# USB_Isolator.net
KiCad netlist of a schematic drawn in Altium Designer
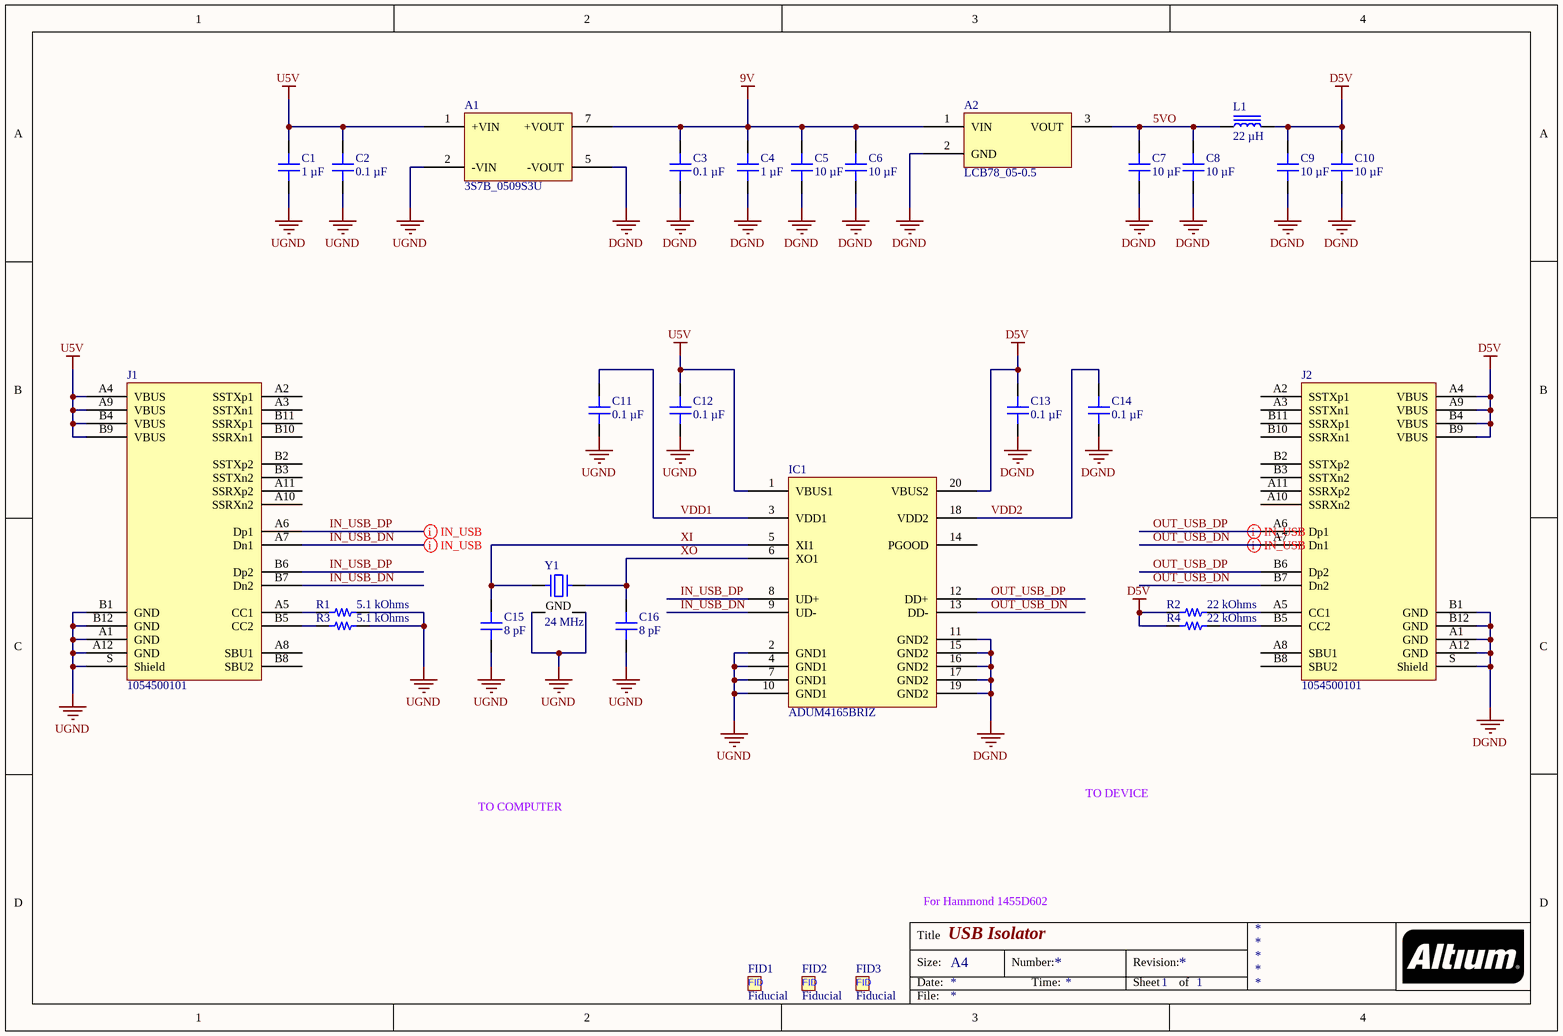
[diagram p0: USB Isolator.SchDoc]

(export (version "E")
  (design (tool "Eeschema 10.0.6"))
  (components
    (comp (ref "A1")
      (value "3S7B_0509S3U")
      (footprint "GAPTEC 3S7B_3U SINGLE")
      (description "DC-DC")
      (fields (field (name "MANUFACTURER") "GAPTEC Electronic"))
      (libsource (lib "altiumlibrary.com") (part "GAPTEC 3S7B_3U SINGLE"))
    )
    (comp (ref "A2")
      (value "LCB78_05-0.5")
      (footprint "GAPTEC LCB78_0.5")
      (description "DC-DC POL")
      (fields (field (name "MANUFACTURER") "GAPTEC Electronic"))
      (libsource (lib "altiumlibrary.com") (part "GAPTEC LCB78"))
    )
    (comp (ref "C1")
      (value "1 µF")
      (footprint "CAP 0603_1608")
      (description "CAP CER 1UF 25V X7R 0603")
      (fields
        (field (name "PART NUMBER") "GCM188R71E105KA64D")
        (field (name "MANUFACTURER") "Murata Electronics")
      )
      (libsource (lib "altiumlibrary.com") (part "Capacitor"))
    )
    (comp (ref "C2")
      (value "0.1 µF")
      (footprint "CAP 0603_1608")
      (description "CAP CER 0.1UF 50V X7R 0603")
      (fields
        (field (name "PART NUMBER") "CL10B104KB8NNNC")
        (field (name "MANUFACTURER") "Samsung Electro-Mechanics")
      )
      (libsource (lib "altiumlibrary.com") (part "Capacitor"))
    )
    (comp (ref "C3")
      (value "0.1 µF")
      (footprint "CAP 0603_1608")
      (description "CAP CER 0.1UF 50V X7R 0603")
      (fields
        (field (name "PART NUMBER") "CL10B104KB8NNNC")
        (field (name "MANUFACTURER") "Samsung Electro-Mechanics")
      )
      (libsource (lib "altiumlibrary.com") (part "Capacitor"))
    )
    (comp (ref "C4")
      (value "1 µF")
      (footprint "CAP 0603_1608")
      (description "CAP CER 1UF 25V X7R 0603")
      (fields
        (field (name "PART NUMBER") "GCM188R71E105KA64D")
        (field (name "MANUFACTURER") "Murata Electronics")
      )
      (libsource (lib "altiumlibrary.com") (part "Capacitor"))
    )
    (comp (ref "C5")
      (value "10 µF")
      (footprint "CAP 1206_3216 - 0.8MM")
      (description "CAP CER 10UF 25V X7R 1206")
      (fields
        (field (name "PART NUMBER") "CL31B106KAHNNNE")
        (field (name "MANUFACTURER") "Samsung Electro-Mechanics")
      )
      (libsource (lib "altiumlibrary.com") (part "Capacitor"))
    )
    (comp (ref "C6")
      (value "10 µF")
      (footprint "CAP 1206_3216 - 0.8MM")
      (description "CAP CER 10UF 25V X7R 1206")
      (fields
        (field (name "PART NUMBER") "CL31B106KAHNNNE")
        (field (name "MANUFACTURER") "Samsung Electro-Mechanics")
      )
      (libsource (lib "altiumlibrary.com") (part "Capacitor"))
    )
    (comp (ref "C7")
      (value "10 µF")
      (footprint "CAP 1206_3216 - 0.8MM")
      (description "CAP CER 10UF 25V X7R 1206")
      (fields
        (field (name "PART NUMBER") "CL31B106KAHNNNE")
        (field (name "MANUFACTURER") "Samsung Electro-Mechanics")
      )
      (libsource (lib "altiumlibrary.com") (part "Capacitor"))
    )
    (comp (ref "C8")
      (value "10 µF")
      (footprint "CAP 1206_3216 - 0.8MM")
      (description "CAP CER 10UF 25V X7R 1206")
      (fields
        (field (name "PART NUMBER") "CL31B106KAHNNNE")
        (field (name "MANUFACTURER") "Samsung Electro-Mechanics")
      )
      (libsource (lib "altiumlibrary.com") (part "Capacitor"))
    )
    (comp (ref "C9")
      (value "10 µF")
      (footprint "CAP 1206_3216 - 0.8MM")
      (description "CAP CER 10UF 25V X7R 1206")
      (fields
        (field (name "PART NUMBER") "CL31B106KAHNNNE")
        (field (name "MANUFACTURER") "Samsung Electro-Mechanics")
      )
      (libsource (lib "altiumlibrary.com") (part "Capacitor"))
    )
    (comp (ref "C10")
      (value "10 µF")
      (footprint "CAP 1206_3216 - 0.8MM")
      (description "CAP CER 10UF 25V X7R 1206")
      (fields
        (field (name "PART NUMBER") "CL31B106KAHNNNE")
        (field (name "MANUFACTURER") "Samsung Electro-Mechanics")
      )
      (libsource (lib "altiumlibrary.com") (part "Capacitor"))
    )
    (comp (ref "C11")
      (value "0.1 µF")
      (footprint "CAP 0603_1608")
      (description "CAP CER 0.1UF 50V X7R 0603")
      (fields
        (field (name "PART NUMBER") "CL10B104KB8NNNC")
        (field (name "MANUFACTURER") "Samsung Electro-Mechanics")
      )
      (libsource (lib "altiumlibrary.com") (part "Capacitor"))
    )
    (comp (ref "C12")
      (value "0.1 µF")
      (footprint "CAP 0603_1608")
      (description "CAP CER 0.1UF 50V X7R 0603")
      (fields
        (field (name "PART NUMBER") "CL10B104KB8NNNC")
        (field (name "MANUFACTURER") "Samsung Electro-Mechanics")
      )
      (libsource (lib "altiumlibrary.com") (part "Capacitor"))
    )
    (comp (ref "C13")
      (value "0.1 µF")
      (footprint "CAP 0603_1608")
      (description "CAP CER 0.1UF 50V X7R 0603")
      (fields
        (field (name "PART NUMBER") "CL10B104KB8NNNC")
        (field (name "MANUFACTURER") "Samsung Electro-Mechanics")
      )
      (libsource (lib "altiumlibrary.com") (part "Capacitor"))
    )
    (comp (ref "C14")
      (value "0.1 µF")
      (footprint "CAP 0603_1608")
      (description "CAP CER 0.1UF 50V X7R 0603")
      (fields
        (field (name "PART NUMBER") "CL10B104KB8NNNC")
        (field (name "MANUFACTURER") "Samsung Electro-Mechanics")
      )
      (libsource (lib "altiumlibrary.com") (part "Capacitor"))
    )
    (comp (ref "C15")
      (value "8 pF")
      (footprint "CAP 0603_1608")
      (description "CAP CER 8PF 50V C0G 0603")
      (fields
        (field (name "PART NUMBER") "CGA3E2C0G1H080D080AA")
        (field (name "MANUFACTURER") "TDK Corporation")
      )
      (libsource (lib "altiumlibrary.com") (part "Capacitor"))
    )
    (comp (ref "C16")
      (value "8 pF")
      (footprint "CAP 0603_1608")
      (description "CAP CER 8PF 50V C0G 0603")
      (fields
        (field (name "PART NUMBER") "CGA3E2C0G1H080D080AA")
        (field (name "MANUFACTURER") "TDK Corporation")
      )
      (libsource (lib "altiumlibrary.com") (part "Capacitor"))
    )
    (comp (ref "FID1")
      (value "Fiducial")
      (footprint "Fiducial-1mm")
      (libsource (lib "CelestialUseful") (part "Fiducial"))
    )
    (comp (ref "FID2")
      (value "Fiducial")
      (footprint "Fiducial-1mm")
      (libsource (lib "CelestialUseful") (part "Fiducial"))
    )
    (comp (ref "FID3")
      (value "Fiducial")
      (footprint "Fiducial-1mm")
      (libsource (lib "CelestialUseful") (part "Fiducial"))
    )
    (comp (ref "IC1")
      (value "ADUM4165BRIZ")
      (footprint "ANALOG SOIC-20 RI-20-1")
      (description "5KV 480MBPS USB DIG ISOLATOR HOS")
      (fields (field (name "MANUFACTURER") "Analog Devices Inc."))
      (libsource (lib "altiumlibrary.com") (part "ANALOG DEVICES ADUM4165"))
    )
    (comp (ref "J1")
      (value "1054500101")
      (footprint "Molex 1054500101")
      (description "CONN RCP USB3.1 TYPEC 24P SMD RA")
      (fields (field (name "MANUFACTURER") "Molex"))
      (libsource (lib "") (part "USB 3.0 Type C_1"))
    )
    (comp (ref "J2")
      (value "1054500101")
      (footprint "Molex 1054500101")
      (description "CONN RCP USB3.1 TYPEC 24P SMD RA")
      (fields (field (name "MANUFACTURER") "Molex"))
      (libsource (lib "altiumlibrary.com") (part "USB 3.0 Type C"))
    )
    (comp (ref "L1")
      (value "22 µH")
      (footprint "TDK VLCF4028-2")
      (description "FIXED IND 22UH 710MA 140MOHM SMD")
      (fields
        (field (name "PART NUMBER") "VLCF5028T-220MR71-2")
        (field (name "MANUFACTURER") "TDK Corporation")
      )
      (libsource (lib "altiumlibrary.com") (part "Inductor"))
    )
    (comp (ref "R1")
      (value "5.1 kOhms")
      (footprint "RES 0603_1608")
      (description "RES 5.1K OHM 1% 1/10W 0603")
      (fields
        (field (name "PART NUMBER") "RK73H1JTTD5101F")
        (field (name "MANUFACTURER") "KOA Speer Electronics, Inc.")
      )
      (libsource (lib "altiumlibrary.com") (part "Resistor"))
    )
    (comp (ref "R2")
      (value "22 kOhms")
      (footprint "RES 0603_1608")
      (description "RES 22K OHM 1% 1/10W 0603")
      (fields (field (name "PART NUMBER") "RC0603FR-1322KL") (field (name "MANUFACTURER") "Yageo"))
      (libsource (lib "altiumlibrary.com") (part "Resistor"))
    )
    (comp (ref "R3")
      (value "5.1 kOhms")
      (footprint "RES 0603_1608")
      (description "RES 5.1K OHM 1% 1/10W 0603")
      (fields
        (field (name "PART NUMBER") "RK73H1JTTD5101F")
        (field (name "MANUFACTURER") "KOA Speer Electronics, Inc.")
      )
      (libsource (lib "altiumlibrary.com") (part "Resistor"))
    )
    (comp (ref "R4")
      (value "22 kOhms")
      (footprint "RES 0603_1608")
      (description "RES 22K OHM 1% 1/10W 0603")
      (fields (field (name "PART NUMBER") "RC0603FR-1322KL") (field (name "MANUFACTURER") "Yageo"))
      (libsource (lib "altiumlibrary.com") (part "Resistor"))
    )
    (comp (ref "Y1")
      (value "24 MHz")
      (footprint "NDK NX2520SA")
      (description "CRYSTAL 24.0000MHZ 8PF SMD")
      (fields
        (field (name "PART NUMBER") "NX2520SA-24MHZ-EXS00A-CS11339")
        (field (name "MANUFACTURER") "NDK America, Inc.")
      )
      (libsource (lib "altiumlibrary.com") (part "NDK Crystal NX2520SA"))
    )
  )
  (nets
    (net (code "1") (name "/5VO") (class "Default")
      (node (ref "A2") (pin "3") (pinfunction "VOUT_3") (pintype "passive"))
      (node (ref "C7") (pin "2") (pinfunction "2_2") (pintype "passive"))
      (node (ref "C8") (pin "2") (pinfunction "2_2") (pintype "passive"))
      (node (ref "L1") (pin "1") (pinfunction "1_1") (pintype "passive"))
    )
    (net (code "2") (name "/IN_USB_DN") (class "Default")
      (node (ref "IC1") (pin "9") (pinfunction "UD-_9") (pintype "passive"))
      (node (ref "J1") (pin "A7") (pinfunction "Dn1_A7") (pintype "passive"))
      (node (ref "J1") (pin "B7") (pinfunction "Dn2_B7") (pintype "passive"))
    )
    (net (code "3") (name "/IN_USB_DP") (class "Default")
      (node (ref "IC1") (pin "8") (pinfunction "UD+_8") (pintype "passive"))
      (node (ref "J1") (pin "A6") (pinfunction "Dp1_A6") (pintype "passive"))
      (node (ref "J1") (pin "B6") (pinfunction "Dp2_B6") (pintype "passive"))
    )
    (net (code "4") (name "/OUT_USB_DN") (class "Default")
      (node (ref "IC1") (pin "13") (pinfunction "DD-_13") (pintype "passive"))
      (node (ref "J2") (pin "A7") (pinfunction "Dn1_A7") (pintype "passive"))
      (node (ref "J2") (pin "B7") (pinfunction "Dn2_B7") (pintype "passive"))
    )
    (net (code "5") (name "/OUT_USB_DP") (class "Default")
      (node (ref "IC1") (pin "12") (pinfunction "DD+_12") (pintype "passive"))
      (node (ref "J2") (pin "A6") (pinfunction "Dp1_A6") (pintype "passive"))
      (node (ref "J2") (pin "B6") (pinfunction "Dp2_B6") (pintype "passive"))
    )
    (net (code "6") (name "/VDD1") (class "Default")
      (node (ref "C11") (pin "2") (pinfunction "2_2") (pintype "passive"))
      (node (ref "IC1") (pin "3") (pinfunction "VDD1_3") (pintype "passive"))
    )
    (net (code "7") (name "/VDD2") (class "Default")
      (node (ref "C14") (pin "2") (pinfunction "2_2") (pintype "passive"))
      (node (ref "IC1") (pin "18") (pinfunction "VDD2_18") (pintype "passive"))
    )
    (net (code "8") (name "/XI") (class "Default")
      (node (ref "C15") (pin "2") (pinfunction "2_2") (pintype "passive"))
      (node (ref "IC1") (pin "5") (pinfunction "XI1_5") (pintype "passive"))
      (node (ref "Y1") (pin "1") (pinfunction "1_1") (pintype "passive"))
    )
    (net (code "9") (name "/XO") (class "Default")
      (node (ref "C16") (pin "2") (pinfunction "2_2") (pintype "passive"))
      (node (ref "IC1") (pin "6") (pinfunction "XO1_6") (pintype "passive"))
      (node (ref "Y1") (pin "3") (pinfunction "3_3") (pintype "passive"))
    )
    (net (code "10") (name "9V") (class "Default")
      (node (ref "A1") (pin "7") (pinfunction "+VOUT_7") (pintype "passive"))
      (node (ref "A2") (pin "1") (pinfunction "VIN_1") (pintype "passive"))
      (node (ref "C3") (pin "2") (pinfunction "2_2") (pintype "passive"))
      (node (ref "C4") (pin "2") (pinfunction "2_2") (pintype "passive"))
      (node (ref "C5") (pin "2") (pinfunction "2_2") (pintype "passive"))
      (node (ref "C6") (pin "2") (pinfunction "2_2") (pintype "passive"))
    )
    (net (code "11") (name "D5V") (class "Default")
      (node (ref "C10") (pin "2") (pinfunction "2_2") (pintype "passive"))
      (node (ref "C13") (pin "2") (pinfunction "2_2") (pintype "passive"))
      (node (ref "C9") (pin "2") (pinfunction "2_2") (pintype "passive"))
      (node (ref "IC1") (pin "20") (pinfunction "VBUS2_20") (pintype "passive"))
      (node (ref "J2") (pin "A4") (pinfunction "VBUS_A4") (pintype "passive"))
      (node (ref "J2") (pin "A9") (pinfunction "VBUS_A9") (pintype "passive"))
      (node (ref "J2") (pin "B4") (pinfunction "VBUS_B4") (pintype "passive"))
      (node (ref "J2") (pin "B9") (pinfunction "VBUS_B9") (pintype "passive"))
      (node (ref "L1") (pin "2") (pinfunction "2_2") (pintype "passive"))
      (node (ref "R2") (pin "1") (pinfunction "1_1") (pintype "passive"))
      (node (ref "R4") (pin "1") (pinfunction "1_1") (pintype "passive"))
    )
    (net (code "12") (name "DGND") (class "Default")
      (node (ref "A1") (pin "5") (pinfunction "-VOUT_5") (pintype "passive"))
      (node (ref "A2") (pin "2") (pinfunction "GND_2") (pintype "passive"))
      (node (ref "C10") (pin "1") (pinfunction "1_1") (pintype "passive"))
      (node (ref "C13") (pin "1") (pinfunction "1_1") (pintype "passive"))
      (node (ref "C14") (pin "1") (pinfunction "1_1") (pintype "passive"))
      (node (ref "C3") (pin "1") (pinfunction "1_1") (pintype "passive"))
      (node (ref "C4") (pin "1") (pinfunction "1_1") (pintype "passive"))
      (node (ref "C5") (pin "1") (pinfunction "1_1") (pintype "passive"))
      (node (ref "C6") (pin "1") (pinfunction "1_1") (pintype "passive"))
      (node (ref "C7") (pin "1") (pinfunction "1_1") (pintype "passive"))
      (node (ref "C8") (pin "1") (pinfunction "1_1") (pintype "passive"))
      (node (ref "C9") (pin "1") (pinfunction "1_1") (pintype "passive"))
      (node (ref "IC1") (pin "11") (pinfunction "GND2_11") (pintype "passive"))
      (node (ref "IC1") (pin "15") (pinfunction "GND2_15") (pintype "passive"))
      (node (ref "IC1") (pin "16") (pinfunction "GND2_16") (pintype "passive"))
      (node (ref "IC1") (pin "17") (pinfunction "GND2_17") (pintype "passive"))
      (node (ref "IC1") (pin "19") (pinfunction "GND2_19") (pintype "passive"))
      (node (ref "J2") (pin "A1") (pinfunction "GND_A1") (pintype "passive"))
      (node (ref "J2") (pin "A12") (pinfunction "GND_A12") (pintype "passive"))
      (node (ref "J2") (pin "B1") (pinfunction "GND_B1") (pintype "passive"))
      (node (ref "J2") (pin "B12") (pinfunction "GND_B12") (pintype "passive"))
      (node (ref "J2") (pin "S") (pinfunction "Shield_S") (pintype "passive"))
    )
    (net (code "13") (name "Net-(J1-CC1)") (class "Default")
      (node (ref "J1") (pin "A5") (pinfunction "CC1_A5") (pintype "passive"))
      (node (ref "R1") (pin "2") (pinfunction "2_2") (pintype "passive"))
    )
    (net (code "14") (name "Net-(J1-CC2)") (class "Default")
      (node (ref "J1") (pin "B5") (pinfunction "CC2_B5") (pintype "passive"))
      (node (ref "R3") (pin "2") (pinfunction "2_2") (pintype "passive"))
    )
    (net (code "15") (name "Net-(J2-CC1)") (class "Default")
      (node (ref "J2") (pin "A5") (pinfunction "CC1_A5") (pintype "passive"))
      (node (ref "R2") (pin "2") (pinfunction "2_2") (pintype "passive"))
    )
    (net (code "16") (name "Net-(J2-CC2)") (class "Default")
      (node (ref "J2") (pin "B5") (pinfunction "CC2_B5") (pintype "passive"))
      (node (ref "R4") (pin "2") (pinfunction "2_2") (pintype "passive"))
    )
    (net (code "17") (name "U5V") (class "Default")
      (node (ref "A1") (pin "1") (pinfunction "+VIN_1") (pintype "passive"))
      (node (ref "C1") (pin "2") (pinfunction "2_2") (pintype "passive"))
      (node (ref "C12") (pin "2") (pinfunction "2_2") (pintype "passive"))
      (node (ref "C2") (pin "2") (pinfunction "2_2") (pintype "passive"))
      (node (ref "IC1") (pin "1") (pinfunction "VBUS1_1") (pintype "passive"))
      (node (ref "J1") (pin "A4") (pinfunction "VBUS_A4") (pintype "passive"))
      (node (ref "J1") (pin "A9") (pinfunction "VBUS_A9") (pintype "passive"))
      (node (ref "J1") (pin "B4") (pinfunction "VBUS_B4") (pintype "passive"))
      (node (ref "J1") (pin "B9") (pinfunction "VBUS_B9") (pintype "passive"))
    )
    (net (code "18") (name "UGND") (class "Default")
      (node (ref "A1") (pin "2") (pinfunction "-VIN_2") (pintype "passive"))
      (node (ref "C1") (pin "1") (pinfunction "1_1") (pintype "passive"))
      (node (ref "C11") (pin "1") (pinfunction "1_1") (pintype "passive"))
      (node (ref "C12") (pin "1") (pinfunction "1_1") (pintype "passive"))
      (node (ref "C15") (pin "1") (pinfunction "1_1") (pintype "passive"))
      (node (ref "C16") (pin "1") (pinfunction "1_1") (pintype "passive"))
      (node (ref "C2") (pin "1") (pinfunction "1_1") (pintype "passive"))
      (node (ref "IC1") (pin "10") (pinfunction "GND1_10") (pintype "passive"))
      (node (ref "IC1") (pin "2") (pinfunction "GND1_2") (pintype "passive"))
      (node (ref "IC1") (pin "4") (pinfunction "GND1_4") (pintype "passive"))
      (node (ref "IC1") (pin "7") (pinfunction "GND1_7") (pintype "passive"))
      (node (ref "J1") (pin "A1") (pinfunction "GND_A1") (pintype "passive"))
      (node (ref "J1") (pin "A12") (pinfunction "GND_A12") (pintype "passive"))
      (node (ref "J1") (pin "B1") (pinfunction "GND_B1") (pintype "passive"))
      (node (ref "J1") (pin "B12") (pinfunction "GND_B12") (pintype "passive"))
      (node (ref "J1") (pin "S") (pinfunction "Shield_S") (pintype "passive"))
      (node (ref "R1") (pin "1") (pinfunction "1_1") (pintype "passive"))
      (node (ref "R3") (pin "1") (pinfunction "1_1") (pintype "passive"))
      (node (ref "Y1") (pin "2") (pinfunction "GND_2") (pintype "passive"))
      (node (ref "Y1") (pin "4") (pinfunction "GND_4") (pintype "passive"))
    )
    (net (code "19") (name "unconnected-(IC1-PGOOD-Pad14)") (class "Default")
      (node (ref "IC1") (pin "14") (pinfunction "PGOOD_14") (pintype "passive"))
    )
    (net (code "20") (name "unconnected-(J1-SBU1-PadA8)") (class "Default")
      (node (ref "J1") (pin "A8") (pinfunction "SBU1_A8") (pintype "passive"))
    )
    (net (code "21") (name "unconnected-(J1-SBU2-PadB8)") (class "Default")
      (node (ref "J1") (pin "B8") (pinfunction "SBU2_B8") (pintype "passive"))
    )
    (net (code "22") (name "unconnected-(J1-SSRXn1-PadB10)") (class "Default")
      (node (ref "J1") (pin "B10") (pinfunction "SSRXn1_B10") (pintype "passive"))
    )
    (net (code "23") (name "unconnected-(J1-SSRXn2-PadA10)") (class "Default")
      (node (ref "J1") (pin "A10") (pinfunction "SSRXn2_A10") (pintype "passive"))
    )
    (net (code "24") (name "unconnected-(J1-SSRXp1-PadB11)") (class "Default")
      (node (ref "J1") (pin "B11") (pinfunction "SSRXp1_B11") (pintype "passive"))
    )
    (net (code "25") (name "unconnected-(J1-SSRXp2-PadA11)") (class "Default")
      (node (ref "J1") (pin "A11") (pinfunction "SSRXp2_A11") (pintype "passive"))
    )
    (net (code "26") (name "unconnected-(J1-SSTXn1-PadA3)") (class "Default")
      (node (ref "J1") (pin "A3") (pinfunction "SSTXn1_A3") (pintype "passive"))
    )
    (net (code "27") (name "unconnected-(J1-SSTXn2-PadB3)") (class "Default")
      (node (ref "J1") (pin "B3") (pinfunction "SSTXn2_B3") (pintype "passive"))
    )
    (net (code "28") (name "unconnected-(J1-SSTXp1-PadA2)") (class "Default")
      (node (ref "J1") (pin "A2") (pinfunction "SSTXp1_A2") (pintype "passive"))
    )
    (net (code "29") (name "unconnected-(J1-SSTXp2-PadB2)") (class "Default")
      (node (ref "J1") (pin "B2") (pinfunction "SSTXp2_B2") (pintype "passive"))
    )
    (net (code "30") (name "unconnected-(J2-SBU1-PadA8)") (class "Default")
      (node (ref "J2") (pin "A8") (pinfunction "SBU1_A8") (pintype "passive"))
    )
    (net (code "31") (name "unconnected-(J2-SBU2-PadB8)") (class "Default")
      (node (ref "J2") (pin "B8") (pinfunction "SBU2_B8") (pintype "passive"))
    )
    (net (code "32") (name "unconnected-(J2-SSRXn1-PadB10)") (class "Default")
      (node (ref "J2") (pin "B10") (pinfunction "SSRXn1_B10") (pintype "passive"))
    )
    (net (code "33") (name "unconnected-(J2-SSRXn2-PadA10)") (class "Default")
      (node (ref "J2") (pin "A10") (pinfunction "SSRXn2_A10") (pintype "passive"))
    )
    (net (code "34") (name "unconnected-(J2-SSRXp1-PadB11)") (class "Default")
      (node (ref "J2") (pin "B11") (pinfunction "SSRXp1_B11") (pintype "passive"))
    )
    (net (code "35") (name "unconnected-(J2-SSRXp2-PadA11)") (class "Default")
      (node (ref "J2") (pin "A11") (pinfunction "SSRXp2_A11") (pintype "passive"))
    )
    (net (code "36") (name "unconnected-(J2-SSTXn1-PadA3)") (class "Default")
      (node (ref "J2") (pin "A3") (pinfunction "SSTXn1_A3") (pintype "passive"))
    )
    (net (code "37") (name "unconnected-(J2-SSTXn2-PadB3)") (class "Default")
      (node (ref "J2") (pin "B3") (pinfunction "SSTXn2_B3") (pintype "passive"))
    )
    (net (code "38") (name "unconnected-(J2-SSTXp1-PadA2)") (class "Default")
      (node (ref "J2") (pin "A2") (pinfunction "SSTXp1_A2") (pintype "passive"))
    )
    (net (code "39") (name "unconnected-(J2-SSTXp2-PadB2)") (class "Default")
      (node (ref "J2") (pin "B2") (pinfunction "SSTXp2_B2") (pintype "passive"))
    )
  )
)
